# HIP4082.net
KiCad netlist of a schematic drawn in Altium Designer
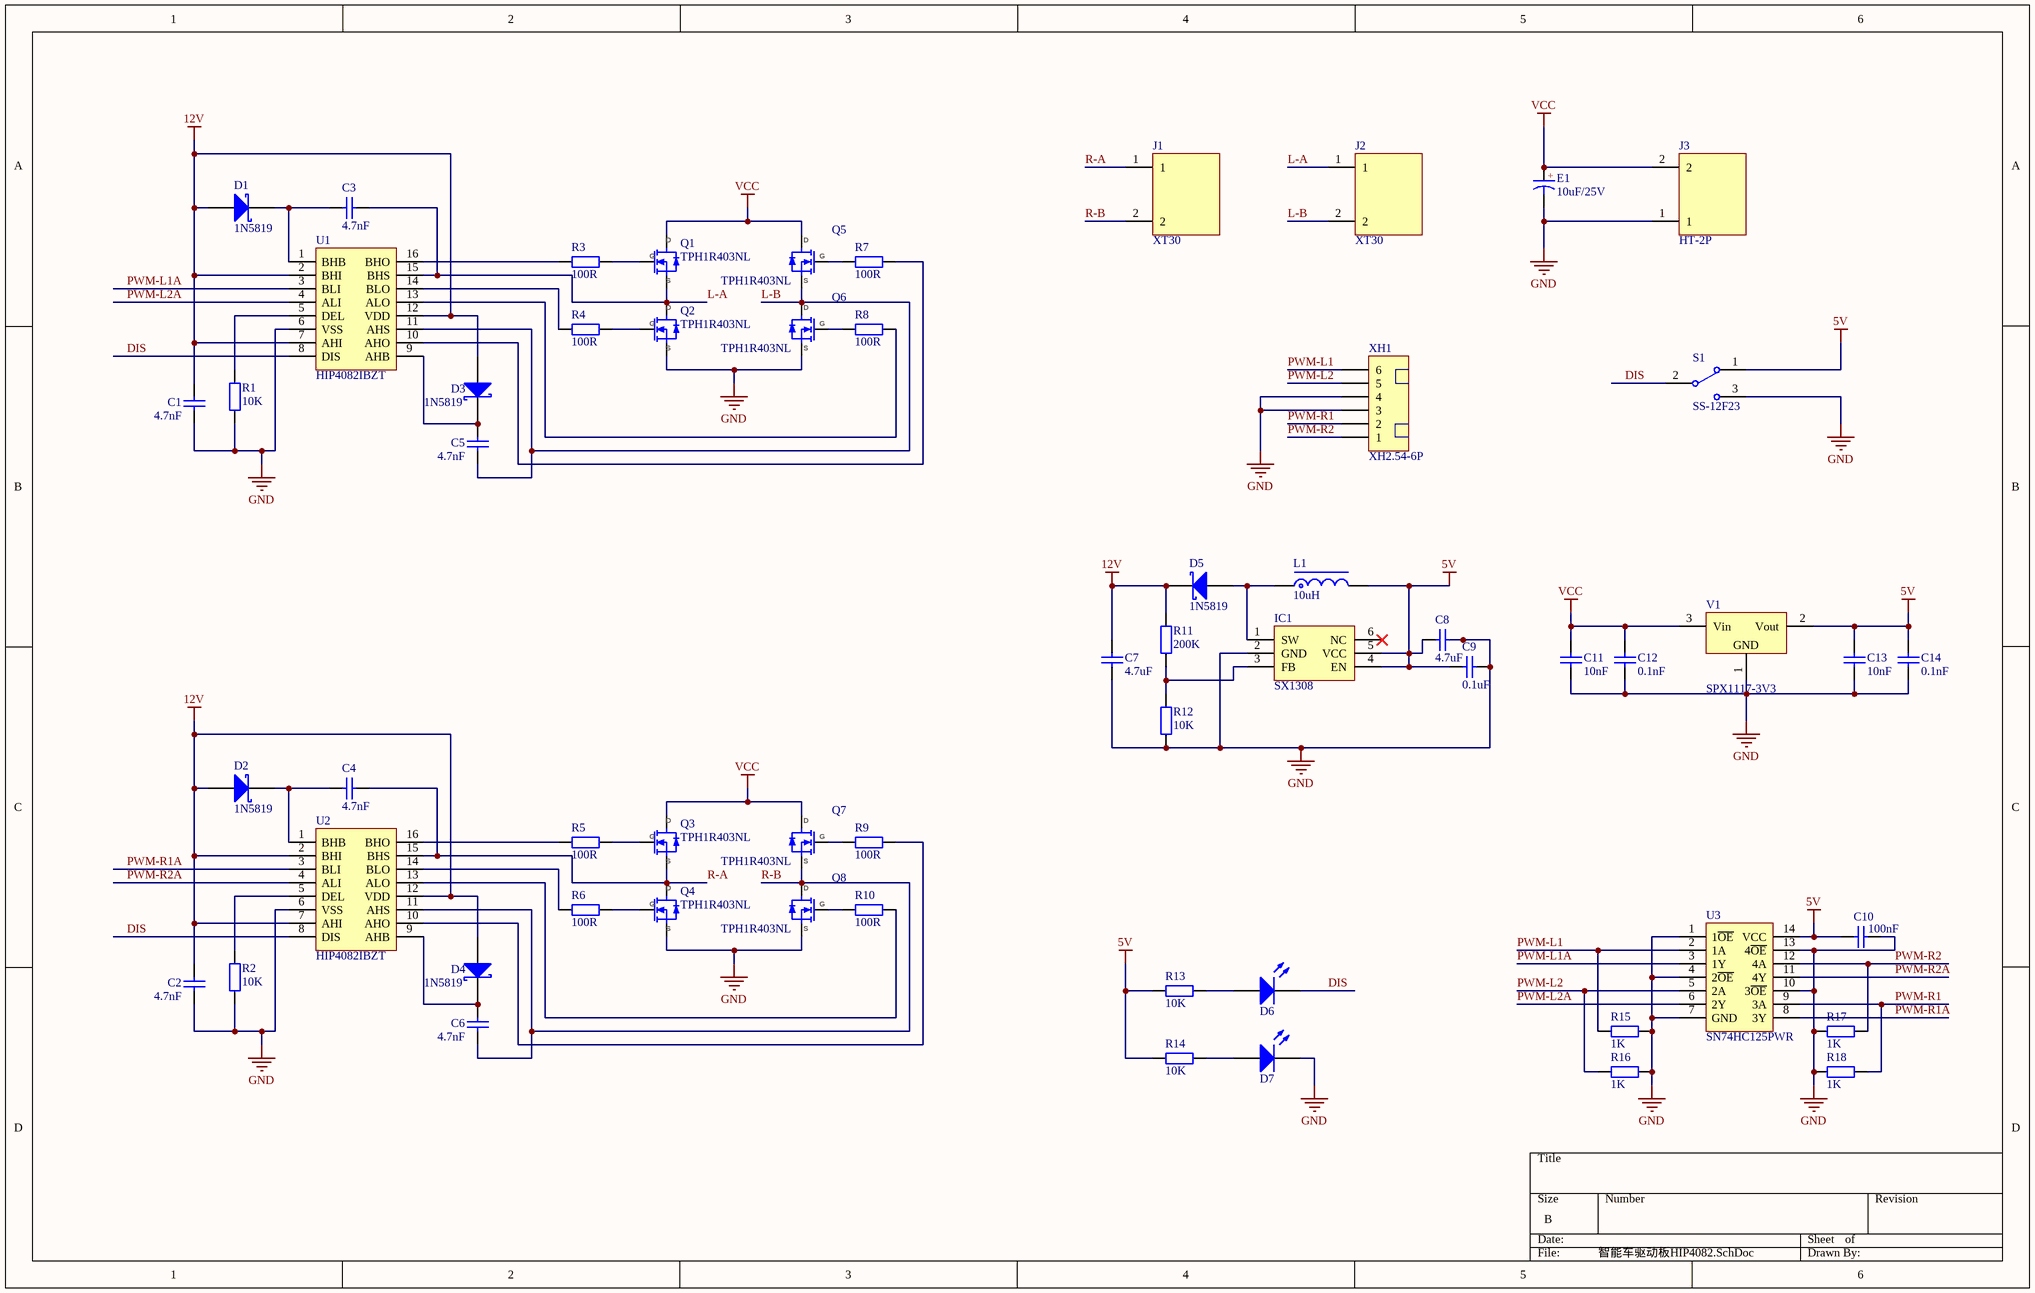
[diagram p0: 智能车驱动板HIP4082.SchDoc]

(export (version "E")
  (design (tool "Eeschema 10.0.6"))
  (components
    (comp (ref "C1")
      (value "4.7nF")
      (footprint "C0603_L")
      (description "贴片电容")
      (libsource (lib "0.1_电容&电感&电阻&保险丝") (part "C-SMD"))
    )
    (comp (ref "C2")
      (value "4.7nF")
      (footprint "C0603_L")
      (description "贴片电容")
      (libsource (lib "0.1_电容&电感&电阻&保险丝") (part "C-SMD"))
    )
    (comp (ref "C3")
      (value "4.7nF")
      (footprint "C0603_L")
      (description "贴片电容")
      (libsource (lib "0.1_电容&电感&电阻&保险丝") (part "C-SMD"))
    )
    (comp (ref "C4")
      (value "4.7nF")
      (footprint "C0603_L")
      (description "贴片电容")
      (libsource (lib "0.1_电容&电感&电阻&保险丝") (part "C-SMD"))
    )
    (comp (ref "C5")
      (value "4.7nF")
      (footprint "C0603_L")
      (description "贴片电容")
      (libsource (lib "0.1_电容&电感&电阻&保险丝") (part "C-SMD"))
    )
    (comp (ref "C6")
      (value "4.7nF")
      (footprint "C0603_L")
      (description "贴片电容")
      (libsource (lib "0.1_电容&电感&电阻&保险丝") (part "C-SMD"))
    )
    (comp (ref "C7")
      (value "4.7uF")
      (footprint "C0603_L")
      (description "贴片电容")
      (libsource (lib "0.1_电容&电感&电阻&保险丝") (part "C-SMD"))
    )
    (comp (ref "C8")
      (value "4.7uF")
      (footprint "C0603_L")
      (description "贴片电容")
      (libsource (lib "0.1_电容&电感&电阻&保险丝") (part "C-SMD"))
    )
    (comp (ref "C9")
      (value "0.1uF")
      (footprint "C0603_L")
      (description "贴片电容")
      (libsource (lib "0.1_电容&电感&电阻&保险丝") (part "C-SMD"))
    )
    (comp (ref "C10")
      (value "100nF")
      (footprint "C0603_L")
      (description "贴片电容")
      (libsource (lib "0.1_电容&电感&电阻&保险丝") (part "C-SMD"))
    )
    (comp (ref "C11")
      (value "10nF")
      (footprint "C0603_L")
      (description "贴片电容")
      (libsource (lib "0.1_电容&电感&电阻&保险丝") (part "C-SMD"))
    )
    (comp (ref "C12")
      (value "0.1nF")
      (footprint "C0603_L")
      (description "贴片电容")
      (libsource (lib "0.1_电容&电感&电阻&保险丝") (part "C-SMD"))
    )
    (comp (ref "C13")
      (value "10nF")
      (footprint "C0603_L")
      (description "贴片电容")
      (libsource (lib "0.1_电容&电感&电阻&保险丝") (part "C-SMD"))
    )
    (comp (ref "C14")
      (value "0.1nF")
      (footprint "C0603_L")
      (description "贴片电容")
      (libsource (lib "0.1_电容&电感&电阻&保险丝") (part "C-SMD"))
    )
    (comp (ref "D1")
      (value "1N5819")
      (footprint "SOD-323")
      (description "肖特基二极管")
      (libsource (lib "0.2_二极管&整流桥") (part "1N5819"))
    )
    (comp (ref "D2")
      (value "1N5819")
      (footprint "SOD-323")
      (description "肖特基二极管")
      (libsource (lib "0.2_二极管&整流桥") (part "1N5819"))
    )
    (comp (ref "D3")
      (value "1N5819")
      (footprint "SOD-323")
      (description "肖特基二极管")
      (libsource (lib "0.2_二极管&整流桥") (part "1N5819"))
    )
    (comp (ref "D4")
      (value "1N5819")
      (footprint "SOD-323")
      (description "肖特基二极管")
      (libsource (lib "0.2_二极管&整流桥") (part "1N5819"))
    )
    (comp (ref "D5")
      (value "1N5819")
      (footprint "SOD-323")
      (description "肖特基二极管")
      (libsource (lib "0.2_二极管&整流桥") (part "1N5819"))
    )
    (comp (ref "D6")
      (value "LED")
      (footprint "LED-0603_R")
      (description "贴片发光二极管")
      (libsource (lib "0.3_LED发光二极管") (part "LED_SMD"))
    )
    (comp (ref "D7")
      (value "LED")
      (footprint "LED-0603_R")
      (description "贴片发光二极管")
      (libsource (lib "0.3_LED发光二极管") (part "LED_SMD"))
    )
    (comp (ref "E1")
      (value "10uF/25V")
      (footprint "CT-2.0*5*8-R")
      (description "直插固态电容")
      (libsource (lib "0.1_电容&电感&电阻&保险丝") (part "C-CS"))
    )
    (comp (ref "IC1")
      (value "SX1308")
      (footprint "SOT23-6N")
      (description "可调2A升压芯片")
      (libsource (lib "1.1_电源类芯片") (part "SX1308"))
    )
    (comp (ref "J1")
      (value "XT30")
      (footprint "XT30-WI")
      (description "30A Low Temperature Rise Fire Retardant Plug")
      (fields (field (name "MANUFACTURER_PART_NUMBER") "XT30PW-M"))
      (libsource (lib "5.12_XT30&XT60") (part "XT30"))
    )
    (comp (ref "J2")
      (value "XT30")
      (footprint "XT30-WI")
      (description "30A Low Temperature Rise Fire Retardant Plug")
      (fields (field (name "MANUFACTURER_PART_NUMBER") "XT30PW-M"))
      (libsource (lib "5.12_XT30&XT60") (part "XT30"))
    )
    (comp (ref "J3")
      (value "HT-2P")
      (footprint "CZ-5.08-L-Z-2P")
      (description "30A Low Temperature Rise Fire Retardant Plug")
      (fields (field (name "MANUFACTURER_PART_NUMBER") "XT30PW-M"))
      (libsource (lib "5.12_XT30&XT60") (part "XT30PW-M"))
    )
    (comp (ref "L1")
      (value "10uH")
      (footprint "NR2520")
      (description "NR磁胶电感")
      (libsource (lib "0.1_电容&电感&电阻&保险丝") (part "L-NR"))
    )
    (comp (ref "Q1")
      (value "TPH1R403NL")
      (footprint "DFN5x6")
      (description "N沟道MOS")
      (libsource (lib "0.4_场效应管&可控硅") (part "TPH1R403NL"))
    )
    (comp (ref "Q2")
      (value "TPH1R403NL")
      (footprint "DFN5x6")
      (description "N沟道MOS")
      (libsource (lib "0.4_场效应管&可控硅") (part "TPH1R403NL"))
    )
    (comp (ref "Q3")
      (value "TPH1R403NL")
      (footprint "DFN5x6")
      (description "N沟道MOS")
      (libsource (lib "0.4_场效应管&可控硅") (part "TPH1R403NL"))
    )
    (comp (ref "Q4")
      (value "TPH1R403NL")
      (footprint "DFN5x6")
      (description "N沟道MOS")
      (libsource (lib "0.4_场效应管&可控硅") (part "TPH1R403NL"))
    )
    (comp (ref "Q5")
      (value "TPH1R403NL")
      (footprint "DFN5x6")
      (description "N沟道MOS")
      (libsource (lib "0.4_场效应管&可控硅") (part "TPH1R403NL"))
    )
    (comp (ref "Q6")
      (value "TPH1R403NL")
      (footprint "DFN5x6")
      (description "N沟道MOS")
      (libsource (lib "0.4_场效应管&可控硅") (part "TPH1R403NL"))
    )
    (comp (ref "Q7")
      (value "TPH1R403NL")
      (footprint "DFN5x6")
      (description "N沟道MOS")
      (libsource (lib "0.4_场效应管&可控硅") (part "TPH1R403NL"))
    )
    (comp (ref "Q8")
      (value "TPH1R403NL")
      (footprint "DFN5x6")
      (description "N沟道MOS")
      (libsource (lib "0.4_场效应管&可控硅") (part "TPH1R403NL"))
    )
    (comp (ref "R1")
      (value "10K")
      (footprint "R0603_L")
      (description "贴片电阻")
      (libsource (lib "0.1_电容&电感&电阻&保险丝") (part "R-SMD"))
    )
    (comp (ref "R2")
      (value "10K")
      (footprint "R0603_L")
      (description "贴片电阻")
      (libsource (lib "0.1_电容&电感&电阻&保险丝") (part "R-SMD"))
    )
    (comp (ref "R3")
      (value "100R")
      (footprint "R0603_L")
      (description "贴片电阻")
      (libsource (lib "0.1_电容&电感&电阻&保险丝") (part "R-SMD"))
    )
    (comp (ref "R4")
      (value "100R")
      (footprint "R0603_L")
      (description "贴片电阻")
      (libsource (lib "0.1_电容&电感&电阻&保险丝") (part "R-SMD"))
    )
    (comp (ref "R5")
      (value "100R")
      (footprint "R0603_L")
      (description "贴片电阻")
      (libsource (lib "0.1_电容&电感&电阻&保险丝") (part "R-SMD"))
    )
    (comp (ref "R6")
      (value "100R")
      (footprint "R0603_L")
      (description "贴片电阻")
      (libsource (lib "0.1_电容&电感&电阻&保险丝") (part "R-SMD"))
    )
    (comp (ref "R7")
      (value "100R")
      (footprint "R0603_L")
      (description "贴片电阻")
      (libsource (lib "0.1_电容&电感&电阻&保险丝") (part "R-SMD"))
    )
    (comp (ref "R8")
      (value "100R")
      (footprint "R0603_L")
      (description "贴片电阻")
      (libsource (lib "0.1_电容&电感&电阻&保险丝") (part "R-SMD"))
    )
    (comp (ref "R9")
      (value "100R")
      (footprint "R0603_L")
      (description "贴片电阻")
      (libsource (lib "0.1_电容&电感&电阻&保险丝") (part "R-SMD"))
    )
    (comp (ref "R10")
      (value "100R")
      (footprint "R0603_L")
      (description "贴片电阻")
      (libsource (lib "0.1_电容&电感&电阻&保险丝") (part "R-SMD"))
    )
    (comp (ref "R11")
      (value "200K")
      (footprint "R0603_L")
      (description "贴片电阻")
      (libsource (lib "0.1_电容&电感&电阻&保险丝") (part "R-SMD"))
    )
    (comp (ref "R12")
      (value "10K")
      (footprint "R0603_L")
      (description "贴片电阻")
      (libsource (lib "0.1_电容&电感&电阻&保险丝") (part "R-SMD"))
    )
    (comp (ref "R13")
      (value "10K")
      (footprint "R0603_L")
      (description "贴片电阻")
      (libsource (lib "0.1_电容&电感&电阻&保险丝") (part "R-SMD"))
    )
    (comp (ref "R14")
      (value "10K")
      (footprint "R0603_L")
      (description "贴片电阻")
      (libsource (lib "0.1_电容&电感&电阻&保险丝") (part "R-SMD"))
    )
    (comp (ref "R15")
      (value "1K")
      (footprint "R0603_L")
      (description "贴片电阻")
      (libsource (lib "0.1_电容&电感&电阻&保险丝") (part "R-SMD"))
    )
    (comp (ref "R16")
      (value "1K")
      (footprint "R0603_L")
      (description "贴片电阻")
      (libsource (lib "0.1_电容&电感&电阻&保险丝") (part "R-SMD"))
    )
    (comp (ref "R17")
      (value "1K")
      (footprint "R0603_L")
      (description "贴片电阻")
      (libsource (lib "0.1_电容&电感&电阻&保险丝") (part "R-SMD"))
    )
    (comp (ref "R18")
      (value "1K")
      (footprint "R0603_L")
      (description "贴片电阻")
      (libsource (lib "0.1_电容&电感&电阻&保险丝") (part "R-SMD"))
    )
    (comp (ref "S1")
      (value "SS-12F23")
      (footprint "SS-12F23")
      (description "1路波动开关")
      (libsource (lib "0.8_按键&开关") (part "SSW-1P"))
    )
    (comp (ref "U1")
      (value "HIP4082IBZT")
      (footprint "SOP16_M")
      (description "全桥MOSFET驱动芯片 SOP-16")
      (libsource (lib "1.3_电机驱动芯片") (part "HIP4082IBZT"))
    )
    (comp (ref "U2")
      (value "HIP4082IBZT")
      (footprint "SOP16_M")
      (description "全桥MOSFET驱动芯片 SOP-16")
      (libsource (lib "1.3_电机驱动芯片") (part "HIP4082IBZT"))
    )
    (comp (ref "U3")
      (value "SN74HC125PWR")
      (footprint "TSSOP14")
      (description "三态输出的四路缓冲器")
      (libsource (lib "1.7_隔离类芯片") (part "SN74HC125PWR"))
    )
    (comp (ref "V1")
      (value "SPX1117-3V3")
      (footprint "SOT223_L")
      (description "三端稳压芯片")
      (libsource (lib "1.1_电源类芯片") (part "SPX1117"))
    )
    (comp (ref "XH1")
      (value "XH2.54-6P")
      (footprint "XH2.54-6P-WI")
      (libsource (lib "5.2_XH") (part "XH2.54-6P"))
    )
  )
  (nets
    (net (code "1") (name "/DIS") (class "Default")
      (node (ref "D6") (pin "2") (pinfunction "K_2") (pintype "passive"))
      (node (ref "S1") (pin "2") (pinfunction "2_2") (pintype "passive"))
      (node (ref "U1") (pin "8") (pinfunction "DIS_8") (pintype "passive"))
      (node (ref "U2") (pin "8") (pinfunction "DIS_8") (pintype "passive"))
    )
    (net (code "2") (name "/L-A") (class "Default")
      (node (ref "C3") (pin "1") (pinfunction "1_1") (pintype "passive"))
      (node (ref "J2") (pin "1") (pinfunction "1_1") (pintype "passive"))
      (node (ref "Q1") (pin "3") (pinfunction "S_3") (pintype "passive"))
      (node (ref "Q2") (pin "1") (pinfunction "D_1") (pintype "passive"))
      (node (ref "U1") (pin "15") (pinfunction "BHS_15") (pintype "passive"))
    )
    (net (code "3") (name "/L-B") (class "Default")
      (node (ref "C5") (pin "1") (pinfunction "1_1") (pintype "passive"))
      (node (ref "J2") (pin "2") (pinfunction "2_2") (pintype "passive"))
      (node (ref "Q5") (pin "3") (pinfunction "S_3") (pintype "passive"))
      (node (ref "Q6") (pin "1") (pinfunction "D_1") (pintype "passive"))
      (node (ref "U1") (pin "11") (pinfunction "AHS_11") (pintype "passive"))
    )
    (net (code "4") (name "/PWM-L1") (class "Default")
      (node (ref "R15") (pin "1") (pinfunction "1_1") (pintype "passive"))
      (node (ref "U3") (pin "2") (pinfunction "1A_2") (pintype "passive"))
      (node (ref "XH1") (pin "6") (pinfunction "6_6") (pintype "passive"))
    )
    (net (code "5") (name "/PWM-L1A") (class "Default")
      (node (ref "U1") (pin "3") (pinfunction "BLI_3") (pintype "passive"))
      (node (ref "U3") (pin "3") (pinfunction "1Y_3") (pintype "passive"))
    )
    (net (code "6") (name "/PWM-L2") (class "Default")
      (node (ref "R16") (pin "1") (pinfunction "1_1") (pintype "passive"))
      (node (ref "U3") (pin "5") (pinfunction "2A_5") (pintype "passive"))
      (node (ref "XH1") (pin "5") (pinfunction "5_5") (pintype "passive"))
    )
    (net (code "7") (name "/PWM-L2A") (class "Default")
      (node (ref "U1") (pin "4") (pinfunction "ALI_4") (pintype "passive"))
      (node (ref "U3") (pin "6") (pinfunction "2Y_6") (pintype "passive"))
    )
    (net (code "8") (name "/PWM-R1") (class "Default")
      (node (ref "R18") (pin "2") (pinfunction "2_2") (pintype "passive"))
      (node (ref "U3") (pin "9") (pinfunction "3A_9") (pintype "passive"))
      (node (ref "XH1") (pin "2") (pinfunction "2_2") (pintype "passive"))
    )
    (net (code "9") (name "/PWM-R1A") (class "Default")
      (node (ref "U2") (pin "3") (pinfunction "BLI_3") (pintype "passive"))
      (node (ref "U3") (pin "8") (pinfunction "3Y_8") (pintype "passive"))
    )
    (net (code "10") (name "/PWM-R2") (class "Default")
      (node (ref "R17") (pin "2") (pinfunction "2_2") (pintype "passive"))
      (node (ref "U3") (pin "12") (pinfunction "4A_12") (pintype "passive"))
      (node (ref "XH1") (pin "1") (pinfunction "1_1") (pintype "passive"))
    )
    (net (code "11") (name "/PWM-R2A") (class "Default")
      (node (ref "U2") (pin "4") (pinfunction "ALI_4") (pintype "passive"))
      (node (ref "U3") (pin "11") (pinfunction "4Y_11") (pintype "passive"))
    )
    (net (code "12") (name "/R-A") (class "Default")
      (node (ref "C4") (pin "1") (pinfunction "1_1") (pintype "passive"))
      (node (ref "J1") (pin "1") (pinfunction "1_1") (pintype "passive"))
      (node (ref "Q3") (pin "3") (pinfunction "S_3") (pintype "passive"))
      (node (ref "Q4") (pin "1") (pinfunction "D_1") (pintype "passive"))
      (node (ref "U2") (pin "15") (pinfunction "BHS_15") (pintype "passive"))
    )
    (net (code "13") (name "/R-B") (class "Default")
      (node (ref "C6") (pin "1") (pinfunction "1_1") (pintype "passive"))
      (node (ref "J1") (pin "2") (pinfunction "2_2") (pintype "passive"))
      (node (ref "Q7") (pin "3") (pinfunction "S_3") (pintype "passive"))
      (node (ref "Q8") (pin "1") (pinfunction "D_1") (pintype "passive"))
      (node (ref "U2") (pin "11") (pinfunction "AHS_11") (pintype "passive"))
    )
    (net (code "14") (name "5V") (class "Default")
      (node (ref "C10") (pin "1") (pinfunction "1_1") (pintype "passive"))
      (node (ref "C13") (pin "2") (pinfunction "2_2") (pintype "passive"))
      (node (ref "C14") (pin "2") (pinfunction "2_2") (pintype "passive"))
      (node (ref "C8") (pin "1") (pinfunction "1_1") (pintype "passive"))
      (node (ref "C9") (pin "1") (pinfunction "1_1") (pintype "passive"))
      (node (ref "IC1") (pin "4") (pinfunction "EN_4") (pintype "passive"))
      (node (ref "IC1") (pin "5") (pinfunction "VCC_5") (pintype "passive"))
      (node (ref "L1") (pin "2") (pinfunction "2_2") (pintype "passive"))
      (node (ref "R13") (pin "1") (pinfunction "1_1") (pintype "passive"))
      (node (ref "R14") (pin "1") (pinfunction "1_1") (pintype "passive"))
      (node (ref "S1") (pin "1") (pinfunction "1_1") (pintype "passive"))
      (node (ref "U3") (pin "14") (pinfunction "VCC_14") (pintype "passive"))
      (node (ref "V1") (pin "2") (pinfunction "Vout_2") (pintype "passive"))
    )
    (net (code "15") (name "12V") (class "Default")
      (node (ref "C1") (pin "2") (pinfunction "2_2") (pintype "passive"))
      (node (ref "C2") (pin "2") (pinfunction "2_2") (pintype "passive"))
      (node (ref "C7") (pin "2") (pinfunction "2_2") (pintype "passive"))
      (node (ref "D1") (pin "1") (pinfunction "A_1") (pintype "passive"))
      (node (ref "D2") (pin "1") (pinfunction "A_1") (pintype "passive"))
      (node (ref "D3") (pin "1") (pinfunction "A_1") (pintype "passive"))
      (node (ref "D4") (pin "1") (pinfunction "A_1") (pintype "passive"))
      (node (ref "D5") (pin "2") (pinfunction "K_2") (pintype "passive"))
      (node (ref "R11") (pin "2") (pinfunction "2_2") (pintype "passive"))
      (node (ref "U1") (pin "12") (pinfunction "VDD_12") (pintype "passive"))
      (node (ref "U1") (pin "2") (pinfunction "BHI_2") (pintype "passive"))
      (node (ref "U1") (pin "7") (pinfunction "AHI_7") (pintype "passive"))
      (node (ref "U2") (pin "12") (pinfunction "VDD_12") (pintype "passive"))
      (node (ref "U2") (pin "2") (pinfunction "BHI_2") (pintype "passive"))
      (node (ref "U2") (pin "7") (pinfunction "AHI_7") (pintype "passive"))
    )
    (net (code "16") (name "GND") (class "Default")
      (node (ref "C1") (pin "1") (pinfunction "1_1") (pintype "passive"))
      (node (ref "C10") (pin "2") (pinfunction "2_2") (pintype "passive"))
      (node (ref "C11") (pin "1") (pinfunction "1_1") (pintype "passive"))
      (node (ref "C12") (pin "1") (pinfunction "1_1") (pintype "passive"))
      (node (ref "C13") (pin "1") (pinfunction "1_1") (pintype "passive"))
      (node (ref "C14") (pin "1") (pinfunction "1_1") (pintype "passive"))
      (node (ref "C2") (pin "1") (pinfunction "1_1") (pintype "passive"))
      (node (ref "C7") (pin "1") (pinfunction "1_1") (pintype "passive"))
      (node (ref "C8") (pin "2") (pinfunction "2_2") (pintype "passive"))
      (node (ref "C9") (pin "2") (pinfunction "2_2") (pintype "passive"))
      (node (ref "D7") (pin "2") (pinfunction "K_2") (pintype "passive"))
      (node (ref "E1") (pin "2") (pinfunction "2_2") (pintype "passive"))
      (node (ref "IC1") (pin "2") (pinfunction "GND_2") (pintype "passive"))
      (node (ref "J3") (pin "1") (pinfunction "1_1") (pintype "passive"))
      (node (ref "Q2") (pin "3") (pinfunction "S_3") (pintype "passive"))
      (node (ref "Q4") (pin "3") (pinfunction "S_3") (pintype "passive"))
      (node (ref "Q6") (pin "3") (pinfunction "S_3") (pintype "passive"))
      (node (ref "Q8") (pin "3") (pinfunction "S_3") (pintype "passive"))
      (node (ref "R1") (pin "1") (pinfunction "1_1") (pintype "passive"))
      (node (ref "R12") (pin "1") (pinfunction "1_1") (pintype "passive"))
      (node (ref "R15") (pin "2") (pinfunction "2_2") (pintype "passive"))
      (node (ref "R16") (pin "2") (pinfunction "2_2") (pintype "passive"))
      (node (ref "R17") (pin "1") (pinfunction "1_1") (pintype "passive"))
      (node (ref "R18") (pin "1") (pinfunction "1_1") (pintype "passive"))
      (node (ref "R2") (pin "1") (pinfunction "1_1") (pintype "passive"))
      (node (ref "S1") (pin "3") (pinfunction "3_3") (pintype "passive"))
      (node (ref "U1") (pin "6") (pinfunction "VSS_6") (pintype "passive"))
      (node (ref "U2") (pin "6") (pinfunction "VSS_6") (pintype "passive"))
      (node (ref "U3") (pin "1") (pinfunction "1~{OE}_1") (pintype "passive"))
      (node (ref "U3") (pin "10") (pinfunction "3~{OE}_10") (pintype "passive"))
      (node (ref "U3") (pin "13") (pinfunction "4~{OE}_13") (pintype "passive"))
      (node (ref "U3") (pin "4") (pinfunction "2~{OE}_4") (pintype "passive"))
      (node (ref "U3") (pin "7") (pinfunction "GND_7") (pintype "passive"))
      (node (ref "V1") (pin "1") (pinfunction "GND_1") (pintype "passive"))
      (node (ref "XH1") (pin "3") (pinfunction "3_3") (pintype "passive"))
      (node (ref "XH1") (pin "4") (pinfunction "4_4") (pintype "passive"))
    )
    (net (code "17") (name "Net-(D1-K)") (class "Default")
      (node (ref "C3") (pin "2") (pinfunction "2_2") (pintype "passive"))
      (node (ref "D1") (pin "2") (pinfunction "K_2") (pintype "passive"))
      (node (ref "U1") (pin "1") (pinfunction "BHB_1") (pintype "passive"))
    )
    (net (code "18") (name "Net-(D2-K)") (class "Default")
      (node (ref "C4") (pin "2") (pinfunction "2_2") (pintype "passive"))
      (node (ref "D2") (pin "2") (pinfunction "K_2") (pintype "passive"))
      (node (ref "U2") (pin "1") (pinfunction "BHB_1") (pintype "passive"))
    )
    (net (code "19") (name "Net-(D3-K)") (class "Default")
      (node (ref "C5") (pin "2") (pinfunction "2_2") (pintype "passive"))
      (node (ref "D3") (pin "2") (pinfunction "K_2") (pintype "passive"))
      (node (ref "U1") (pin "9") (pinfunction "AHB_9") (pintype "passive"))
    )
    (net (code "20") (name "Net-(D4-K)") (class "Default")
      (node (ref "C6") (pin "2") (pinfunction "2_2") (pintype "passive"))
      (node (ref "D4") (pin "2") (pinfunction "K_2") (pintype "passive"))
      (node (ref "U2") (pin "9") (pinfunction "AHB_9") (pintype "passive"))
    )
    (net (code "21") (name "Net-(D5-A)") (class "Default")
      (node (ref "D5") (pin "1") (pinfunction "A_1") (pintype "passive"))
      (node (ref "IC1") (pin "1") (pinfunction "SW_1") (pintype "passive"))
      (node (ref "L1") (pin "1") (pinfunction "1_1") (pintype "passive"))
    )
    (net (code "22") (name "Net-(D6-A)") (class "Default")
      (node (ref "D6") (pin "1") (pinfunction "A_1") (pintype "passive"))
      (node (ref "R13") (pin "2") (pinfunction "2_2") (pintype "passive"))
    )
    (net (code "23") (name "Net-(D7-A)") (class "Default")
      (node (ref "D7") (pin "1") (pinfunction "A_1") (pintype "passive"))
      (node (ref "R14") (pin "2") (pinfunction "2_2") (pintype "passive"))
    )
    (net (code "24") (name "Net-(IC1-FB)") (class "Default")
      (node (ref "IC1") (pin "3") (pinfunction "FB_3") (pintype "passive"))
      (node (ref "R11") (pin "1") (pinfunction "1_1") (pintype "passive"))
      (node (ref "R12") (pin "2") (pinfunction "2_2") (pintype "passive"))
    )
    (net (code "25") (name "Net-(Q1-G)") (class "Default")
      (node (ref "Q1") (pin "2") (pinfunction "G_2") (pintype "passive"))
      (node (ref "R3") (pin "2") (pinfunction "2_2") (pintype "passive"))
    )
    (net (code "26") (name "Net-(Q2-G)") (class "Default")
      (node (ref "Q2") (pin "2") (pinfunction "G_2") (pintype "passive"))
      (node (ref "R4") (pin "2") (pinfunction "2_2") (pintype "passive"))
    )
    (net (code "27") (name "Net-(Q3-G)") (class "Default")
      (node (ref "Q3") (pin "2") (pinfunction "G_2") (pintype "passive"))
      (node (ref "R5") (pin "2") (pinfunction "2_2") (pintype "passive"))
    )
    (net (code "28") (name "Net-(Q4-G)") (class "Default")
      (node (ref "Q4") (pin "2") (pinfunction "G_2") (pintype "passive"))
      (node (ref "R6") (pin "2") (pinfunction "2_2") (pintype "passive"))
    )
    (net (code "29") (name "Net-(Q5-G)") (class "Default")
      (node (ref "Q5") (pin "2") (pinfunction "G_2") (pintype "passive"))
      (node (ref "R7") (pin "1") (pinfunction "1_1") (pintype "passive"))
    )
    (net (code "30") (name "Net-(Q6-G)") (class "Default")
      (node (ref "Q6") (pin "2") (pinfunction "G_2") (pintype "passive"))
      (node (ref "R8") (pin "1") (pinfunction "1_1") (pintype "passive"))
    )
    (net (code "31") (name "Net-(Q7-G)") (class "Default")
      (node (ref "Q7") (pin "2") (pinfunction "G_2") (pintype "passive"))
      (node (ref "R9") (pin "1") (pinfunction "1_1") (pintype "passive"))
    )
    (net (code "32") (name "Net-(Q8-G)") (class "Default")
      (node (ref "Q8") (pin "2") (pinfunction "G_2") (pintype "passive"))
      (node (ref "R10") (pin "1") (pinfunction "1_1") (pintype "passive"))
    )
    (net (code "33") (name "Net-(U1-AHO)") (class "Default")
      (node (ref "R7") (pin "2") (pinfunction "2_2") (pintype "passive"))
      (node (ref "U1") (pin "10") (pinfunction "AHO_10") (pintype "passive"))
    )
    (net (code "34") (name "Net-(U1-ALO)") (class "Default")
      (node (ref "R8") (pin "2") (pinfunction "2_2") (pintype "passive"))
      (node (ref "U1") (pin "13") (pinfunction "ALO_13") (pintype "passive"))
    )
    (net (code "35") (name "Net-(U1-BHO)") (class "Default")
      (node (ref "R3") (pin "1") (pinfunction "1_1") (pintype "passive"))
      (node (ref "U1") (pin "16") (pinfunction "BHO_16") (pintype "passive"))
    )
    (net (code "36") (name "Net-(U1-BLO)") (class "Default")
      (node (ref "R4") (pin "1") (pinfunction "1_1") (pintype "passive"))
      (node (ref "U1") (pin "14") (pinfunction "BLO_14") (pintype "passive"))
    )
    (net (code "37") (name "Net-(U1-DEL)") (class "Default")
      (node (ref "R1") (pin "2") (pinfunction "2_2") (pintype "passive"))
      (node (ref "U1") (pin "5") (pinfunction "DEL_5") (pintype "passive"))
    )
    (net (code "38") (name "Net-(U2-AHO)") (class "Default")
      (node (ref "R9") (pin "2") (pinfunction "2_2") (pintype "passive"))
      (node (ref "U2") (pin "10") (pinfunction "AHO_10") (pintype "passive"))
    )
    (net (code "39") (name "Net-(U2-ALO)") (class "Default")
      (node (ref "R10") (pin "2") (pinfunction "2_2") (pintype "passive"))
      (node (ref "U2") (pin "13") (pinfunction "ALO_13") (pintype "passive"))
    )
    (net (code "40") (name "Net-(U2-BHO)") (class "Default")
      (node (ref "R5") (pin "1") (pinfunction "1_1") (pintype "passive"))
      (node (ref "U2") (pin "16") (pinfunction "BHO_16") (pintype "passive"))
    )
    (net (code "41") (name "Net-(U2-BLO)") (class "Default")
      (node (ref "R6") (pin "1") (pinfunction "1_1") (pintype "passive"))
      (node (ref "U2") (pin "14") (pinfunction "BLO_14") (pintype "passive"))
    )
    (net (code "42") (name "Net-(U2-DEL)") (class "Default")
      (node (ref "R2") (pin "2") (pinfunction "2_2") (pintype "passive"))
      (node (ref "U2") (pin "5") (pinfunction "DEL_5") (pintype "passive"))
    )
    (net (code "43") (name "VCC") (class "Default")
      (node (ref "C11") (pin "2") (pinfunction "2_2") (pintype "passive"))
      (node (ref "C12") (pin "2") (pinfunction "2_2") (pintype "passive"))
      (node (ref "E1") (pin "1") (pinfunction "1_1") (pintype "passive"))
      (node (ref "J3") (pin "2") (pinfunction "2_2") (pintype "passive"))
      (node (ref "Q1") (pin "1") (pinfunction "D_1") (pintype "passive"))
      (node (ref "Q3") (pin "1") (pinfunction "D_1") (pintype "passive"))
      (node (ref "Q5") (pin "1") (pinfunction "D_1") (pintype "passive"))
      (node (ref "Q7") (pin "1") (pinfunction "D_1") (pintype "passive"))
      (node (ref "V1") (pin "3") (pinfunction "Vin_3") (pintype "passive"))
    )
    (net (code "44") (name "unconnected-(IC1-NC-Pad6)") (class "Default")
      (node (ref "IC1") (pin "6") (pinfunction "NC_6") (pintype "passive+no_connect"))
    )
  )
)
